# Amp.net
KiCad netlist of a schematic drawn in Altium Designer
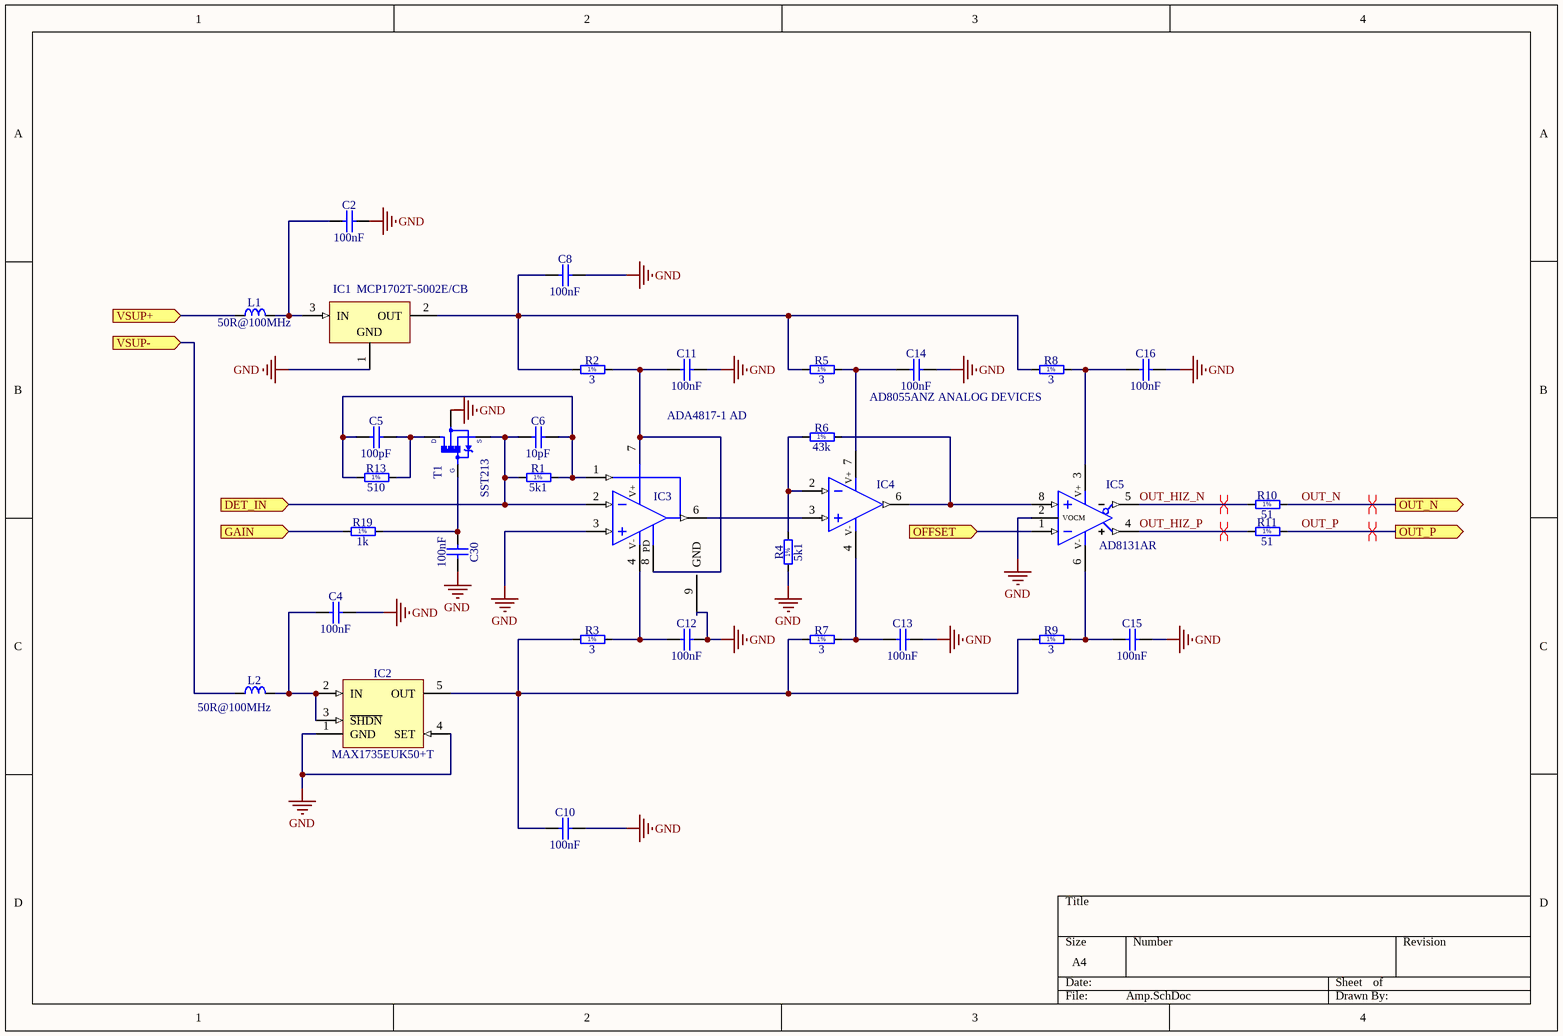
[diagram p0: Amp.SchDoc]

(export (version "E")
  (design (tool "Eeschema 10.0.6"))
  (components
    (comp (ref "C2")
      (value "100nF")
      (footprint "CAPC2012X135N")
      (description "Non-polarised capacitor")
      (fields
        (field (name "PART NUMBER") "CC0805_100NF_50V_10%_X7R")
        (field (name "VOLTAGE") "50V")
        (field (name "AUTHOR") "CERN DEM JLC")
      )
      (libsource (lib "Capacitors") (part "Capacitor - non polarized"))
    )
    (comp (ref "C4")
      (value "100nF")
      (footprint "CAPC2012X135N")
      (description "Non-polarised capacitor")
      (fields
        (field (name "PART NUMBER") "CC0805_100NF_50V_10%_X7R")
        (field (name "VOLTAGE") "50V")
        (field (name "AUTHOR") "CERN DEM JLC")
      )
      (libsource (lib "Capacitors") (part "Capacitor - non polarized"))
    )
    (comp (ref "C5")
      (value "100pF")
      (footprint "CAPC2012X88N")
      (description "Non-polarised capacitor")
      (fields
        (field (name "PART NUMBER") "CC0805_100PF_50V_5%_C0G_KEMET_C0805C101J5GACAUTO")
        (field (name "VOLTAGE") "50V")
        (field (name "AUTHOR") "CERN DEM BC")
      )
      (libsource (lib "Capacitors") (part "Capacitor - non polarized"))
    )
    (comp (ref "C6")
      (value "10pF")
      (footprint "CAPC2012X135N")
      (description "Non-polarised capacitor")
      (fields
        (field (name "PART NUMBER") "CC0805_10PF_50V_1%_NP0")
        (field (name "VOLTAGE") "50V")
        (field (name "AUTHOR") "CERN DEM MR")
      )
      (libsource (lib "Capacitors") (part "Capacitor - non polarized"))
    )
    (comp (ref "C8")
      (value "100nF")
      (footprint "CAPC2012X135N")
      (description "Non-polarised capacitor")
      (fields
        (field (name "PART NUMBER") "CC0805_100NF_50V_10%_X7R")
        (field (name "VOLTAGE") "50V")
        (field (name "AUTHOR") "CERN DEM JLC")
      )
      (libsource (lib "Capacitors") (part "Capacitor - non polarized"))
    )
    (comp (ref "C10")
      (value "100nF")
      (footprint "CAPC2012X135N")
      (description "Non-polarised capacitor")
      (fields
        (field (name "PART NUMBER") "CC0805_100NF_50V_10%_X7R")
        (field (name "VOLTAGE") "50V")
        (field (name "AUTHOR") "CERN DEM JLC")
      )
      (libsource (lib "Capacitors") (part "Capacitor - non polarized"))
    )
    (comp (ref "C11")
      (value "100nF")
      (footprint "CAPC2012X135N")
      (description "Non-polarised capacitor")
      (fields
        (field (name "PART NUMBER") "CC0805_100NF_50V_10%_X7R")
        (field (name "VOLTAGE") "50V")
        (field (name "AUTHOR") "CERN DEM JLC")
      )
      (libsource (lib "Capacitors") (part "Capacitor - non polarized"))
    )
    (comp (ref "C12")
      (value "100nF")
      (footprint "CAPC2012X135N")
      (description "Non-polarised capacitor")
      (fields
        (field (name "PART NUMBER") "CC0805_100NF_50V_10%_X7R")
        (field (name "VOLTAGE") "50V")
        (field (name "AUTHOR") "CERN DEM JLC")
      )
      (libsource (lib "Capacitors") (part "Capacitor - non polarized"))
    )
    (comp (ref "C13")
      (value "100nF")
      (footprint "CAPC2012X135N")
      (description "Non-polarised capacitor")
      (fields
        (field (name "PART NUMBER") "CC0805_100NF_50V_10%_X7R")
        (field (name "VOLTAGE") "50V")
        (field (name "AUTHOR") "CERN DEM JLC")
      )
      (libsource (lib "Capacitors") (part "Capacitor - non polarized"))
    )
    (comp (ref "C14")
      (value "100nF")
      (footprint "CAPC2012X135N")
      (description "Non-polarised capacitor")
      (fields
        (field (name "PART NUMBER") "CC0805_100NF_50V_10%_X7R")
        (field (name "VOLTAGE") "50V")
        (field (name "AUTHOR") "CERN DEM JLC")
      )
      (libsource (lib "Capacitors") (part "Capacitor - non polarized"))
    )
    (comp (ref "C15")
      (value "100nF")
      (footprint "CAPC2012X135N")
      (description "Non-polarised capacitor")
      (fields
        (field (name "PART NUMBER") "CC0805_100NF_50V_10%_X7R")
        (field (name "VOLTAGE") "50V")
        (field (name "AUTHOR") "CERN DEM JLC")
      )
      (libsource (lib "Capacitors") (part "Capacitor - non polarized"))
    )
    (comp (ref "C16")
      (value "100nF")
      (footprint "CAPC2012X135N")
      (description "Non-polarised capacitor")
      (fields
        (field (name "PART NUMBER") "CC0805_100NF_50V_10%_X7R")
        (field (name "VOLTAGE") "50V")
        (field (name "AUTHOR") "CERN DEM JLC")
      )
      (libsource (lib "Capacitors") (part "Capacitor - non polarized"))
    )
    (comp (ref "C30")
      (value "100nF")
      (footprint "CAPC2012X135N")
      (description "Non-polarised capacitor")
      (fields
        (field (name "PART NUMBER") "CC0805_100NF_50V_10%_X7R")
        (field (name "VOLTAGE") "50V")
        (field (name "AUTHOR") "CERN DEM JLC")
      )
      (libsource (lib "Capacitors") (part "Capacitor - non polarized"))
    )
    (comp (ref "IC1")
      (value "MCP1702T-5002E/CB")
      (footprint "SOT95P255X145-3N")
      (description "3-Terminal Regulator 1=GND 2=OUT 3=IN")
      (fields (field (name "MANUFACTURER") "MICROCHIP TECHNOLOGY") (field (name "AUTHOR") "CERN DEM JLC"))
      (libsource (lib "ICs And Semiconductors") (part "REG3 1GND-2OUT-3IN"))
    )
    (comp (ref "IC2")
      (value "MAX1735EUK50+T")
      (footprint "SOT95P280X145-5N")
      (description "200mA, Negative-Output, Low-Dropout Linear Regulator")
      (fields (field (name "MANUFACTURER") "MAXIM") (field (name "AUTHOR") "CERN DEM JLC"))
      (libsource (lib "ICs And Semiconductors") (part "MAX1735"))
    )
    (comp (ref "IC3")
      (value "ADA4817-1 AD")
      (footprint "SOIC127P600X175-9N-S229")
      (fields (field (name "MANUFACTURER") "AD"))
      (libsource (lib "Additional") (part "ADA4817-1"))
    )
    (comp (ref "IC4")
      (value "AD8055ANZ ANALOG DEVICES")
      (footprint "SOIC127P600X175-8N")
      (fields
        (field (name "PART NUMBER") "AD8055ANZ")
        (field (name "MANUFACTURER") "ANALOG DEVICES")
        (field (name "AUTHOR") "CERN DEM JLC")
      )
      (libsource (lib "Additional") (part "AD8055"))
    )
    (comp (ref "IC5")
      (value "AD8131AR")
      (footprint "SOIC127P600X175-8N")
      (description "Differential Amplifier")
      (fields (field (name "MANUFACTURER") "ANALOG DEVICES") (field (name "AUTHOR") "CERN DEM JMW"))
      (libsource (lib "ICs And Semiconductors") (part "Differential Amplifier Type1"))
    )
    (comp (ref "L1")
      (value "50R@100MHz")
      (footprint "IND_MURATA_BLM31PG")
      (description "Inductor")
      (fields
        (field (name "PART NUMBER") "IND1206_MURATA_BLM31PG500SN1")
        (field (name "POWER") "3.5A")
        (field (name "AUTHOR") "CERN DEM JLC")
      )
      (libsource (lib "Inductors & Transformers") (part "Inductor"))
    )
    (comp (ref "L2")
      (value "50R@100MHz")
      (footprint "IND_MURATA_BLM31PG")
      (description "Inductor")
      (fields
        (field (name "PART NUMBER") "IND1206_MURATA_BLM31PG500SN1")
        (field (name "POWER") "3.5A")
        (field (name "AUTHOR") "CERN DEM JLC")
      )
      (libsource (lib "Inductors & Transformers") (part "Inductor"))
    )
    (comp (ref "R1")
      (value "5k1")
      (footprint "RESC2012X60N")
      (description "Resistor - 1%")
      (fields
        (field (name "PART NUMBER") "R0805_5K1_1%_0.125W_100PPM")
        (field (name "POWER") "0.125W")
        (field (name "AUTHOR") "CERN DEM JLC")
      )
      (libsource (lib "Resistors") (part "Resistor - 1%"))
    )
    (comp (ref "R2")
      (value "3")
      (footprint "RESC2012X60N")
      (description "Resistor - 1%")
      (fields
        (field (name "PART NUMBER") "R0805_3R_1%_0.125W_200PPM")
        (field (name "POWER") "0.125W")
        (field (name "AUTHOR") "CERN DEM JLC")
      )
      (libsource (lib "Resistors") (part "Resistor - 1%"))
    )
    (comp (ref "R3")
      (value "3")
      (footprint "RESC2012X60N")
      (description "Resistor - 1%")
      (fields
        (field (name "PART NUMBER") "R0805_3R_1%_0.125W_200PPM")
        (field (name "POWER") "0.125W")
        (field (name "AUTHOR") "CERN DEM JLC")
      )
      (libsource (lib "Resistors") (part "Resistor - 1%"))
    )
    (comp (ref "R4")
      (value "5k1")
      (footprint "RESC2012X60N")
      (description "Resistor - 1%")
      (fields
        (field (name "PART NUMBER") "R0805_5K1_1%_0.125W_100PPM")
        (field (name "POWER") "0.125W")
        (field (name "AUTHOR") "CERN DEM JLC")
      )
      (libsource (lib "Resistors") (part "Resistor - 1%"))
    )
    (comp (ref "R5")
      (value "3")
      (footprint "RESC2012X60N")
      (description "Resistor - 1%")
      (fields
        (field (name "PART NUMBER") "R0805_3R_1%_0.125W_200PPM")
        (field (name "POWER") "0.125W")
        (field (name "AUTHOR") "CERN DEM JLC")
      )
      (libsource (lib "Resistors") (part "Resistor - 1%"))
    )
    (comp (ref "R6")
      (value "43k")
      (footprint "RESC2012X60N")
      (description "Resistor - 1%")
      (fields
        (field (name "PART NUMBER") "R0805_43K_1%_0.125W_100PPM")
        (field (name "POWER") "0.125W")
        (field (name "AUTHOR") "CERN DEM JLC")
      )
      (libsource (lib "Resistors") (part "Resistor - 1%"))
    )
    (comp (ref "R7")
      (value "3")
      (footprint "RESC2012X60N")
      (description "Resistor - 1%")
      (fields
        (field (name "PART NUMBER") "R0805_3R_1%_0.125W_200PPM")
        (field (name "POWER") "0.125W")
        (field (name "AUTHOR") "CERN DEM JLC")
      )
      (libsource (lib "Resistors") (part "Resistor - 1%"))
    )
    (comp (ref "R8")
      (value "3")
      (footprint "RESC2012X60N")
      (description "Resistor - 1%")
      (fields
        (field (name "PART NUMBER") "R0805_3R_1%_0.125W_200PPM")
        (field (name "POWER") "0.125W")
        (field (name "AUTHOR") "CERN DEM JLC")
      )
      (libsource (lib "Resistors") (part "Resistor - 1%"))
    )
    (comp (ref "R9")
      (value "3")
      (footprint "RESC2012X60N")
      (description "Resistor - 1%")
      (fields
        (field (name "PART NUMBER") "R0805_3R_1%_0.125W_200PPM")
        (field (name "POWER") "0.125W")
        (field (name "AUTHOR") "CERN DEM JLC")
      )
      (libsource (lib "Resistors") (part "Resistor - 1%"))
    )
    (comp (ref "R10")
      (value "51")
      (footprint "RESC2012X60N")
      (description "Resistor - 1%")
      (fields
        (field (name "PART NUMBER") "R0805_51R_1%_0.125W_100PPM")
        (field (name "POWER") "0.125W")
        (field (name "AUTHOR") "CERN DEM JLC")
      )
      (libsource (lib "Resistors") (part "Resistor - 1%"))
    )
    (comp (ref "R11")
      (value "51")
      (footprint "RESC2012X60N")
      (description "Resistor - 1%")
      (fields
        (field (name "PART NUMBER") "R0805_51R_1%_0.125W_100PPM")
        (field (name "POWER") "0.125W")
        (field (name "AUTHOR") "CERN DEM JLC")
      )
      (libsource (lib "Resistors") (part "Resistor - 1%"))
    )
    (comp (ref "R13")
      (value "510")
      (footprint "RESC2012X60N")
      (description "Resistor - 1%")
      (fields
        (field (name "PART NUMBER") "R0805_510R_1%_0.125W_100PPM")
        (field (name "POWER") "0.125W")
        (field (name "AUTHOR") "CERN DEM JLC")
      )
      (libsource (lib "Resistors") (part "Resistor - 1%"))
    )
    (comp (ref "R19")
      (value "1k")
      (footprint "RESC2012X60N")
      (description "Resistor - 1%")
      (fields
        (field (name "PART NUMBER") "R0805_1K_1%_0.125W_100PPM")
        (field (name "POWER") "0.125W")
        (field (name "AUTHOR") "CERN DEM JLC")
      )
      (libsource (lib "Resistors") (part "Resistor - 1%"))
    )
    (comp (ref "T1")
      (value "SST213")
      (footprint "SOT143N")
      (description "N-CHANNEL DMOS FET WITH ZENER DIODE")
      (fields (field (name "MANUFACTURER") "CALOGIC") (field (name "AUTHOR") "CERN DEM MR"))
      (libsource (lib "ICs And Semiconductors") (part "SST213"))
    )
  )
  (nets
    (net (code "1") (name "/DET_IN") (class "Default")
      (node (ref "C6") (pin "1") (pinfunction "1_1") (pintype "passive"))
      (node (ref "IC3") (pin "2") (pinfunction "IN-_2") (pintype "input"))
      (node (ref "R1") (pin "1") (pinfunction "1_1") (pintype "passive"))
      (node (ref "T1") (pin "2") (pinfunction "S_2") (pintype "passive"))
    )
    (net (code "2") (name "/GAIN") (class "Default")
      (node (ref "R19") (pin "1") (pinfunction "1_1") (pintype "passive"))
    )
    (net (code "3") (name "/OFFSET") (class "Default")
      (node (ref "IC5") (pin "1") (pinfunction "IN-_1") (pintype "input"))
    )
    (net (code "4") (name "/OUT_HIZ_N") (class "Default")
      (node (ref "IC5") (pin "5") (pinfunction "VOUT-_5") (pintype "output"))
      (node (ref "R10") (pin "1") (pinfunction "1_1") (pintype "passive"))
    )
    (net (code "5") (name "/OUT_HIZ_P") (class "Default")
      (node (ref "IC5") (pin "4") (pinfunction "VOUT+_4") (pintype "output"))
      (node (ref "R11") (pin "1") (pinfunction "1_1") (pintype "passive"))
    )
    (net (code "6") (name "/OUT_N") (class "Default")
      (node (ref "R10") (pin "2") (pinfunction "2_2") (pintype "passive"))
    )
    (net (code "7") (name "/OUT_P") (class "Default")
      (node (ref "R11") (pin "2") (pinfunction "2_2") (pintype "passive"))
    )
    (net (code "8") (name "/VSUP+") (class "Default")
      (node (ref "L1") (pin "1") (pinfunction "1_1") (pintype "passive"))
    )
    (net (code "9") (name "/VSUP-") (class "Default")
      (node (ref "L2") (pin "1") (pinfunction "1_1") (pintype "passive"))
    )
    (net (code "10") (name "GND") (class "Default")
      (node (ref "C10") (pin "2") (pinfunction "2_2") (pintype "passive"))
      (node (ref "C11") (pin "2") (pinfunction "2_2") (pintype "passive"))
      (node (ref "C12") (pin "2") (pinfunction "2_2") (pintype "passive"))
      (node (ref "C13") (pin "2") (pinfunction "2_2") (pintype "passive"))
      (node (ref "C14") (pin "2") (pinfunction "2_2") (pintype "passive"))
      (node (ref "C15") (pin "2") (pinfunction "2_2") (pintype "passive"))
      (node (ref "C16") (pin "2") (pinfunction "2_2") (pintype "passive"))
      (node (ref "C2") (pin "2") (pinfunction "2_2") (pintype "passive"))
      (node (ref "C30") (pin "2") (pinfunction "2_2") (pintype "passive"))
      (node (ref "C4") (pin "2") (pinfunction "2_2") (pintype "passive"))
      (node (ref "C8") (pin "2") (pinfunction "2_2") (pintype "passive"))
      (node (ref "IC1") (pin "1") (pinfunction "GND_1") (pintype "power_in"))
      (node (ref "IC2") (pin "1") (pinfunction "GND_1") (pintype "power_in"))
      (node (ref "IC2") (pin "4") (pinfunction "SET_4") (pintype "input"))
      (node (ref "IC3") (pin "3") (pinfunction "IN+_3") (pintype "input"))
      (node (ref "IC3") (pin "9") (pinfunction "GND_9") (pintype "power_in"))
      (node (ref "IC5") (pin "2") (pinfunction "VOCM_2") (pintype "passive"))
      (node (ref "R4") (pin "1") (pinfunction "1_1") (pintype "passive"))
      (node (ref "T1") (pin "1") (pinfunction "BODY_1") (pintype "passive"))
    )
    (net (code "11") (name "Net-(IC1-IN)") (class "Default")
      (node (ref "C2") (pin "1") (pinfunction "1_1") (pintype "passive"))
      (node (ref "IC1") (pin "3") (pinfunction "IN_3") (pintype "input"))
      (node (ref "L1") (pin "2") (pinfunction "2_2") (pintype "passive"))
    )
    (net (code "12") (name "Net-(IC1-OUT)") (class "Default")
      (node (ref "C8") (pin "1") (pinfunction "1_1") (pintype "passive"))
      (node (ref "IC1") (pin "2") (pinfunction "OUT_2") (pintype "power_in"))
      (node (ref "R2") (pin "1") (pinfunction "1_1") (pintype "passive"))
      (node (ref "R5") (pin "1") (pinfunction "1_1") (pintype "passive"))
      (node (ref "R8") (pin "1") (pinfunction "1_1") (pintype "passive"))
    )
    (net (code "13") (name "Net-(IC2-IN)") (class "Default")
      (node (ref "C4") (pin "1") (pinfunction "1_1") (pintype "passive"))
      (node (ref "IC2") (pin "2") (pinfunction "IN_2") (pintype "input"))
      (node (ref "IC2") (pin "3") (pinfunction "~{SHDN}_3") (pintype "input"))
      (node (ref "L2") (pin "2") (pinfunction "2_2") (pintype "passive"))
    )
    (net (code "14") (name "Net-(IC2-OUT)") (class "Default")
      (node (ref "C10") (pin "1") (pinfunction "1_1") (pintype "passive"))
      (node (ref "IC2") (pin "5") (pinfunction "OUT_5") (pintype "power_in"))
      (node (ref "R3") (pin "1") (pinfunction "1_1") (pintype "passive"))
      (node (ref "R7") (pin "1") (pinfunction "1_1") (pintype "passive"))
      (node (ref "R9") (pin "1") (pinfunction "1_1") (pintype "passive"))
    )
    (net (code "15") (name "Net-(IC3-FB)") (class "Default")
      (node (ref "C5") (pin "1") (pinfunction "1_1") (pintype "passive"))
      (node (ref "C6") (pin "2") (pinfunction "2_2") (pintype "passive"))
      (node (ref "IC3") (pin "1") (pinfunction "FB_1") (pintype "input"))
      (node (ref "R1") (pin "2") (pinfunction "2_2") (pintype "passive"))
      (node (ref "R13") (pin "1") (pinfunction "1_1") (pintype "passive"))
    )
    (net (code "16") (name "Net-(IC3-OUT)") (class "Default")
      (node (ref "IC3") (pin "6") (pinfunction "OUT_6") (pintype "output"))
      (node (ref "IC4") (pin "3") (pinfunction "IN+_3") (pintype "input"))
    )
    (net (code "17") (name "Net-(IC3-PD)") (class "Default")
      (node (ref "C11") (pin "1") (pinfunction "1_1") (pintype "passive"))
      (node (ref "IC3") (pin "7") (pinfunction "V+_7") (pintype "power_in"))
      (node (ref "IC3") (pin "8") (pinfunction "PD_8") (pintype "power_in"))
      (node (ref "R2") (pin "2") (pinfunction "2_2") (pintype "passive"))
    )
    (net (code "18") (name "Net-(IC3-V-)") (class "Default")
      (node (ref "C12") (pin "1") (pinfunction "1_1") (pintype "passive"))
      (node (ref "IC3") (pin "4") (pinfunction "V-_4") (pintype "power_in"))
      (node (ref "R3") (pin "2") (pinfunction "2_2") (pintype "passive"))
    )
    (net (code "19") (name "Net-(IC4-IN-)") (class "Default")
      (node (ref "IC4") (pin "2") (pinfunction "IN-_2") (pintype "input"))
      (node (ref "R4") (pin "2") (pinfunction "2_2") (pintype "passive"))
      (node (ref "R6") (pin "1") (pinfunction "1_1") (pintype "passive"))
    )
    (net (code "20") (name "Net-(IC4-OUT)") (class "Default")
      (node (ref "IC4") (pin "6") (pinfunction "OUT_6") (pintype "output"))
      (node (ref "IC5") (pin "8") (pinfunction "IN+_8") (pintype "input"))
      (node (ref "R6") (pin "2") (pinfunction "2_2") (pintype "passive"))
    )
    (net (code "21") (name "Net-(IC4-V+)") (class "Default")
      (node (ref "C14") (pin "1") (pinfunction "1_1") (pintype "passive"))
      (node (ref "IC4") (pin "7") (pinfunction "V+_7") (pintype "power_in"))
      (node (ref "R5") (pin "2") (pinfunction "2_2") (pintype "passive"))
    )
    (net (code "22") (name "Net-(IC4-V-)") (class "Default")
      (node (ref "C13") (pin "1") (pinfunction "1_1") (pintype "passive"))
      (node (ref "IC4") (pin "4") (pinfunction "V-_4") (pintype "power_in"))
      (node (ref "R7") (pin "2") (pinfunction "2_2") (pintype "passive"))
    )
    (net (code "23") (name "Net-(IC5-V+)") (class "Default")
      (node (ref "C16") (pin "1") (pinfunction "1_1") (pintype "passive"))
      (node (ref "IC5") (pin "3") (pinfunction "V+_3") (pintype "power_in"))
      (node (ref "R8") (pin "2") (pinfunction "2_2") (pintype "passive"))
    )
    (net (code "24") (name "Net-(IC5-V-)") (class "Default")
      (node (ref "C15") (pin "1") (pinfunction "1_1") (pintype "passive"))
      (node (ref "IC5") (pin "6") (pinfunction "V-_6") (pintype "power_in"))
      (node (ref "R9") (pin "2") (pinfunction "2_2") (pintype "passive"))
    )
    (net (code "25") (name "Net-(T1-D)") (class "Default")
      (node (ref "C5") (pin "2") (pinfunction "2_2") (pintype "passive"))
      (node (ref "R13") (pin "2") (pinfunction "2_2") (pintype "passive"))
      (node (ref "T1") (pin "3") (pinfunction "D_3") (pintype "passive"))
    )
    (net (code "26") (name "Net-(T1-G)") (class "Default")
      (node (ref "C30") (pin "1") (pinfunction "1_1") (pintype "passive"))
      (node (ref "R19") (pin "2") (pinfunction "2_2") (pintype "passive"))
      (node (ref "T1") (pin "4") (pinfunction "G_4") (pintype "passive"))
    )
  )
)
